# uCCtrl.net
KiCad netlist of a schematic drawn in Altium Designer
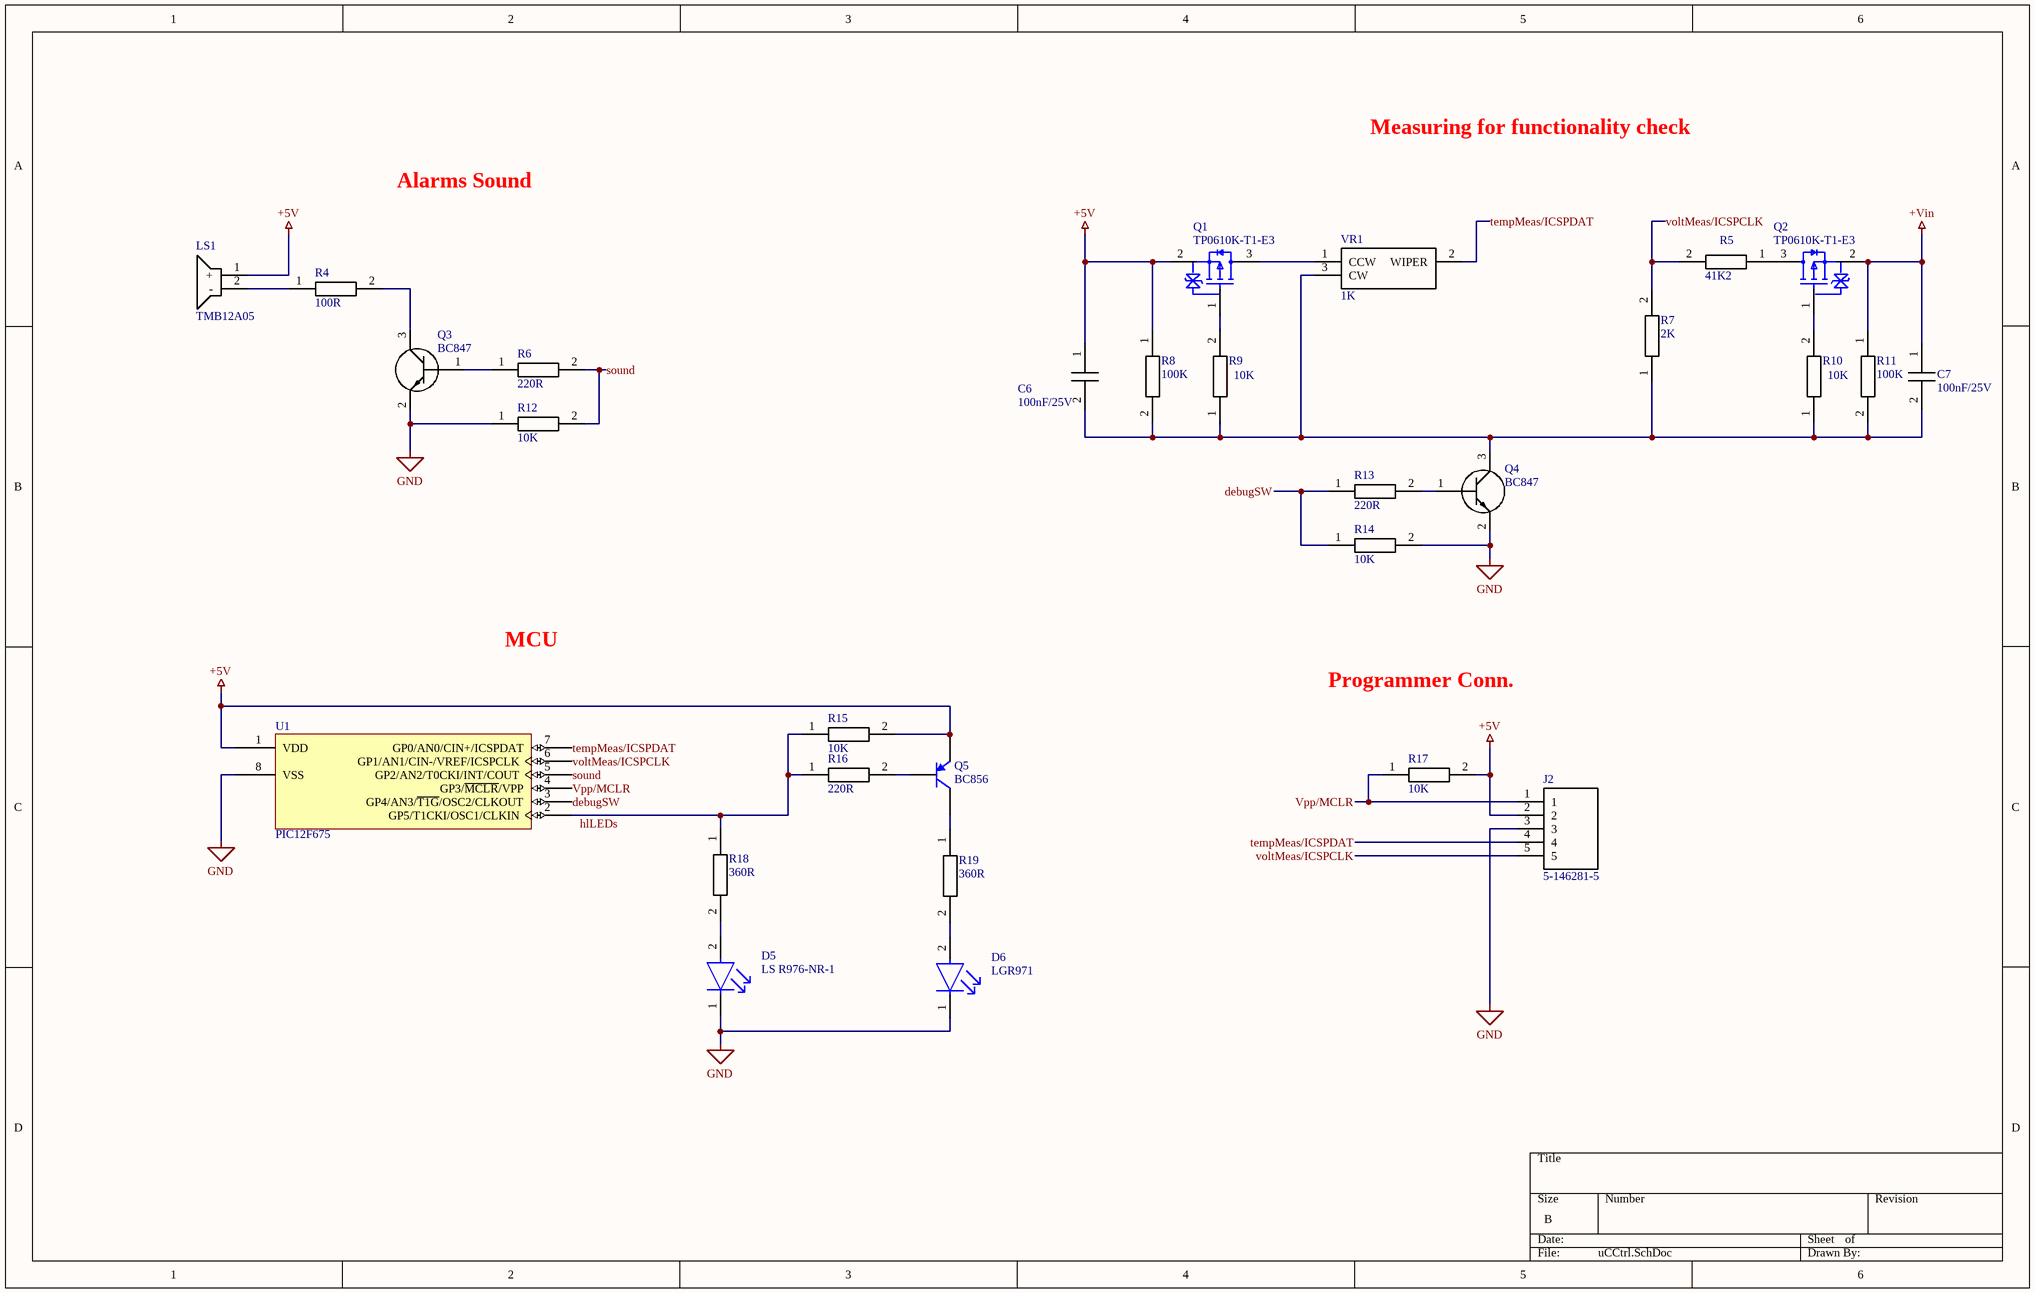
[diagram p0: uCCtrl.SchDoc]

(export (version "E")
  (design (tool "Eeschema 10.0.6"))
  (components
    (comp (ref "C6")
      (value "100nF/25V")
      (footprint "SamacSys:CAPC2012X95N")
      (description "Capacitor")
      (fields (field (name "MANUFACTURER_PART_NUMBER") "GRM219B31E684KA88D"))
      (libsource (lib "*") (part "GRM219B31E684KA88D"))
    )
    (comp (ref "C7")
      (value "100nF/25V")
      (footprint "SamacSys:CAPC2012X95N")
      (description "Capacitor")
      (fields (field (name "MANUFACTURER_PART_NUMBER") "GRM219B31E684KA88D"))
      (libsource (lib "*") (part "GRM219B31E684KA88D"))
    )
    (comp (ref "D5")
      (value "LS R976-NR-1")
      (footprint "FP-LS_R976-MFG")
      (description "LED RED DIFFUSED 0805 SMD")
      (libsource (lib "Altium Content Vault") (part "8706943c75ba83719d021d2fdc84c58"))
    )
    (comp (ref "D6")
      (value "LGR971")
      (footprint "FP-LG_R971-MFG")
      (description "LED GREEN DIFFUSED 0805 SMD")
      (libsource (lib "Altium Content Vault") (part "8706943c75ba83719d021d2fdc84c58"))
    )
    (comp (ref "J2")
      (value "5-146281-5")
      (footprint "SamacSys:HDRV5W67P0X254_1X5_1229X234X821P")
      (description "Connector")
      (fields (field (name "MOUSER PART NUMBER") "571-5-146281-5"))
      (libsource (lib "*") (part "5-146281-5"))
    )
    (comp (ref "LS1")
      (value "TMB12A05")
      (footprint "SamacSys:TMB12A05")
      (description "Loudspeaker or Buzzer")
      (libsource (lib "*") (part "TMB12A05"))
    )
    (comp (ref "Q1")
      (value "TP0610K-T1-E3")
      (footprint "FP-S-03946-MFG")
      (description "MOSFET P-CH 60V 185MA SOT23-3")
      (fields
        (field (name "MANUFACTURER") "Vishay")
        (field (name "OCTOPART") "https://octopart.com/tp0610k-t1-e3-vishay-40944172")
      )
      (libsource (lib "Altium Content Vault") (part "bc9d61678d3f6143cc1ffb3a369bd6c"))
    )
    (comp (ref "Q2")
      (value "TP0610K-T1-E3")
      (footprint "FP-S-03946-MFG")
      (description "MOSFET P-CH 60V 185MA SOT23-3")
      (fields
        (field (name "MANUFACTURER") "Vishay")
        (field (name "OCTOPART") "https://octopart.com/tp0610k-t1-e3-vishay-40944172")
      )
      (libsource (lib "Altium Content Vault") (part "bc9d61678d3f6143cc1ffb3a369bd6c"))
    )
    (comp (ref "Q3")
      (value "BC847")
      (footprint "SamacSys:BC847215")
      (description "Transistor BJT NPN")
      (fields
        (field (name "MANUFACTURER_PART_NUMBER") "BC847,215")
        (field (name "MOUSER PART NUMBER") "771-BC847215")
      )
      (libsource (lib "*") (part "BC847,215"))
    )
    (comp (ref "Q4")
      (value "BC847")
      (footprint "SamacSys:BC847215")
      (description "Transistor BJT NPN")
      (fields
        (field (name "MANUFACTURER_PART_NUMBER") "BC847,215")
        (field (name "MOUSER PART NUMBER") "771-BC847215")
      )
      (libsource (lib "*") (part "BC847,215"))
    )
    (comp (ref "Q5")
      (value "BC856")
      (footprint "NXP-SOT23-3_V")
      (description "PNP General Purpose Transistor, 65 V, -65 to 150 degC, 3-Pin SOT23, RoHS")
      (fields (field (name "MANUFACTURER") "NXP"))
      (libsource (lib "Altium Content Vault") (part "BJT-PNP-BEC-3"))
    )
    (comp (ref "R4")
      (value "100R")
      (footprint "SamacSys:RESC2012X60N")
      (description "Resistor")
      (fields
        (field (name "MANUFACTURER_PART_NUMBER") "CRCW0805100RFKEAHP")
        (field (name "MOUSER PART NUMBER") "71-CRCW0805100RFKEAH")
      )
      (libsource (lib "*") (part "CRCW0805100RFKEAHP"))
    )
    (comp (ref "R5")
      (value "41K2")
      (footprint "SamacSys:RESC2012X65N")
      (description "Resistor")
      (fields (field (name "MANUFACTURER_PART_NUMBER") "CPF0805B41K2E1"))
      (libsource (lib "*") (part "CPF0805B41K2E1"))
    )
    (comp (ref "R6")
      (value "220R")
      (footprint "SamacSys:RESC2012X65N")
      (description "Resistor")
      (fields (field (name "MANUFACTURER_PART_NUMBER") "CPF0805B220RE"))
      (libsource (lib "*") (part "CPF0805B220RE"))
    )
    (comp (ref "R7")
      (value "2K")
      (footprint "SamacSys:RESC2012X65N")
      (description "Resistor")
      (fields
        (field (name "MANUFACTURER_PART_NUMBER") "CPF0805B360RE1")
        (field (name "MOUSER PART NUMBER") "279-CPF0805B360RE1")
      )
      (libsource (lib "*") (part "CPF0805B360RE1"))
    )
    (comp (ref "R8")
      (value "100K")
      (footprint "SamacSys:RESC2012X65N")
      (description "Resistor")
      (fields
        (field (name "MANUFACTURER_PART_NUMBER") "CPF0805B360RE1")
        (field (name "MOUSER PART NUMBER") "279-CPF0805B360RE1")
      )
      (libsource (lib "*") (part "CPF0805B360RE1"))
    )
    (comp (ref "R9")
      (value "10K")
      (footprint "SamacSys:RESC2012X65N")
      (description "Resistor")
      (fields
        (field (name "MANUFACTURER_PART_NUMBER") "CPF0805B360RE1")
        (field (name "MOUSER PART NUMBER") "279-CPF0805B360RE1")
      )
      (libsource (lib "*") (part "CPF0805B360RE1"))
    )
    (comp (ref "R10")
      (value "10K")
      (footprint "SamacSys:RESC2012X65N")
      (description "Resistor")
      (fields
        (field (name "MANUFACTURER_PART_NUMBER") "CPF0805B360RE1")
        (field (name "MOUSER PART NUMBER") "279-CPF0805B360RE1")
      )
      (libsource (lib "*") (part "CPF0805B360RE1"))
    )
    (comp (ref "R11")
      (value "100K")
      (footprint "SamacSys:RESC2012X65N")
      (description "Resistor")
      (fields
        (field (name "MANUFACTURER_PART_NUMBER") "CPF0805B360RE1")
        (field (name "MOUSER PART NUMBER") "279-CPF0805B360RE1")
      )
      (libsource (lib "*") (part "CPF0805B360RE1"))
    )
    (comp (ref "R12")
      (value "10K")
      (footprint "SamacSys:RESC2012X65N")
      (description "Resistor")
      (fields (field (name "MANUFACTURER_PART_NUMBER") "CPF0805B220RE"))
      (libsource (lib "*") (part "CPF0805B220RE"))
    )
    (comp (ref "R13")
      (value "220R")
      (footprint "SamacSys:RESC2012X65N")
      (description "Resistor")
      (fields (field (name "MANUFACTURER_PART_NUMBER") "CPF0805B220RE"))
      (libsource (lib "*") (part "CPF0805B220RE"))
    )
    (comp (ref "R14")
      (value "10K")
      (footprint "SamacSys:RESC2012X65N")
      (description "Resistor")
      (fields (field (name "MANUFACTURER_PART_NUMBER") "CPF0805B220RE"))
      (libsource (lib "*") (part "CPF0805B220RE"))
    )
    (comp (ref "R15")
      (value "10K")
      (footprint "SamacSys:RESC2012X65N")
      (description "Resistor")
      (fields (field (name "MANUFACTURER_PART_NUMBER") "CPF0805B220RE"))
      (libsource (lib "*") (part "CPF0805B220RE"))
    )
    (comp (ref "R16")
      (value "220R")
      (footprint "SamacSys:RESC2012X65N")
      (description "Resistor")
      (fields (field (name "MANUFACTURER_PART_NUMBER") "CPF0805B220RE"))
      (libsource (lib "*") (part "CPF0805B220RE"))
    )
    (comp (ref "R17")
      (value "10K")
      (footprint "SamacSys:RESC2012X65N")
      (description "Resistor")
      (fields
        (field (name "MANUFACTURER_PART_NUMBER") "CPF0805B360RE1")
        (field (name "MOUSER PART NUMBER") "279-CPF0805B360RE1")
      )
      (libsource (lib "*") (part "CPF0805B360RE1"))
    )
    (comp (ref "R18")
      (value "360R")
      (footprint "SamacSys:RESC2012X65N")
      (description "Resistor")
      (fields
        (field (name "MANUFACTURER_PART_NUMBER") "CPF0805B360RE1")
        (field (name "MOUSER PART NUMBER") "279-CPF0805B360RE1")
      )
      (libsource (lib "*") (part "CPF0805B360RE1"))
    )
    (comp (ref "R19")
      (value "360R")
      (footprint "SamacSys:RESC2012X65N")
      (description "Resistor")
      (fields
        (field (name "MANUFACTURER_PART_NUMBER") "CPF0805B360RE1")
        (field (name "MOUSER PART NUMBER") "279-CPF0805B360RE1")
      )
      (libsource (lib "*") (part "CPF0805B360RE1"))
    )
    (comp (ref "U1")
      (value "PIC12F675")
      (footprint "PDIP300-P8")
      (description "FLASH-Based 8-Bit CMOS Microcontroller, 10-Bit A/D, 8-Pin PDIP, Industrial Temperature")
      (libsource (lib "Altium Content Vault") (part "MC-8B-12F675-IL8"))
    )
    (comp (ref "VR1")
      (value "1K")
      (footprint "SamacSys:23SR1KLFTR")
      (description "Variable Resistor")
      (fields (field (name "MANUFACTURER_PART_NUMBER") "23SR1KLFTR"))
      (libsource (lib "*") (part "23SR1KLFTR"))
    )
  )
  (nets
    (net (code "1") (name "+5V") (class "Default")
      (node (ref "C6") (pin "1") (pinfunction "1_1") (pintype "passive"))
      (node (ref "J2") (pin "2") (pinfunction "2_2") (pintype "passive"))
      (node (ref "LS1") (pin "1") (pinfunction "+_1") (pintype "passive"))
      (node (ref "Q1") (pin "2") (pinfunction "S_2") (pintype "passive"))
      (node (ref "Q5") (pin "2") (pinfunction "E_2") (pintype "passive"))
      (node (ref "R15") (pin "2") (pinfunction "2_2") (pintype "passive"))
      (node (ref "R17") (pin "2") (pinfunction "2_2") (pintype "passive"))
      (node (ref "R8") (pin "1") (pinfunction "1_1") (pintype "passive"))
      (node (ref "U1") (pin "1") (pinfunction "VDD_1") (pintype "power_in"))
    )
    (net (code "2") (name "+Vin") (class "Default")
      (node (ref "C7") (pin "1") (pinfunction "1_1") (pintype "passive"))
      (node (ref "Q2") (pin "2") (pinfunction "S_2") (pintype "passive"))
      (node (ref "R11") (pin "1") (pinfunction "1_1") (pintype "passive"))
    )
    (net (code "3") (name "/Vpp{slash}MCLR") (class "Default")
      (node (ref "J2") (pin "1") (pinfunction "1_1") (pintype "passive"))
      (node (ref "R17") (pin "1") (pinfunction "1_1") (pintype "passive"))
      (node (ref "U1") (pin "4") (pinfunction "GP3/~{MCLR}/VPP_4") (pintype "bidirectional"))
    )
    (net (code "4") (name "/debugSW") (class "Default")
      (node (ref "R13") (pin "1") (pinfunction "1_1") (pintype "passive"))
      (node (ref "R14") (pin "1") (pinfunction "1_1") (pintype "passive"))
      (node (ref "U1") (pin "3") (pinfunction "GP4/AN3/~{T1G}/OSC2/CLKOUT_3") (pintype "bidirectional"))
    )
    (net (code "5") (name "/hlLEDs") (class "Default")
      (node (ref "R15") (pin "1") (pinfunction "1_1") (pintype "passive"))
      (node (ref "R16") (pin "1") (pinfunction "1_1") (pintype "passive"))
      (node (ref "R18") (pin "1") (pinfunction "1_1") (pintype "passive"))
      (node (ref "U1") (pin "2") (pinfunction "GP5/T1CKI/OSC1/CLKIN_2") (pintype "bidirectional"))
    )
    (net (code "6") (name "/sound") (class "Default")
      (node (ref "R12") (pin "2") (pinfunction "2_2") (pintype "passive"))
      (node (ref "R6") (pin "2") (pinfunction "2_2") (pintype "passive"))
      (node (ref "U1") (pin "5") (pinfunction "GP2/AN2/T0CKI/INT/COUT_5") (pintype "bidirectional"))
    )
    (net (code "7") (name "/tempMeas{slash}ICSPDAT") (class "Default")
      (node (ref "J2") (pin "4") (pinfunction "4_4") (pintype "passive"))
      (node (ref "U1") (pin "7") (pinfunction "GP0/AN0/CIN+/ICSPDAT_7") (pintype "bidirectional"))
      (node (ref "VR1") (pin "2") (pinfunction "WIPER_2") (pintype "passive"))
    )
    (net (code "8") (name "/voltMeas{slash}ICSPCLK") (class "Default")
      (node (ref "J2") (pin "5") (pinfunction "5_5") (pintype "passive"))
      (node (ref "R5") (pin "2") (pinfunction "2_2") (pintype "passive"))
      (node (ref "R7") (pin "2") (pinfunction "2_2") (pintype "passive"))
      (node (ref "U1") (pin "6") (pinfunction "GP1/AN1/CIN-/VREF/ICSPCLK_6") (pintype "bidirectional"))
    )
    (net (code "9") (name "GND") (class "Default")
      (node (ref "D5") (pin "1") (pinfunction "C_1") (pintype "passive"))
      (node (ref "D6") (pin "1") (pinfunction "C_1") (pintype "passive"))
      (node (ref "J2") (pin "3") (pinfunction "3_3") (pintype "passive"))
      (node (ref "Q3") (pin "2") (pinfunction "E_2") (pintype "passive"))
      (node (ref "Q4") (pin "2") (pinfunction "E_2") (pintype "passive"))
      (node (ref "R12") (pin "1") (pinfunction "1_1") (pintype "passive"))
      (node (ref "R14") (pin "2") (pinfunction "2_2") (pintype "passive"))
      (node (ref "U1") (pin "8") (pinfunction "VSS_8") (pintype "power_in"))
    )
    (net (code "10") (name "Net-(D5-A)") (class "Default")
      (node (ref "D5") (pin "2") (pinfunction "A_2") (pintype "passive"))
      (node (ref "R18") (pin "2") (pinfunction "2_2") (pintype "passive"))
    )
    (net (code "11") (name "Net-(D6-A)") (class "Default")
      (node (ref "D6") (pin "2") (pinfunction "A_2") (pintype "passive"))
      (node (ref "R19") (pin "2") (pinfunction "2_2") (pintype "passive"))
    )
    (net (code "12") (name "Net-(LS1--)") (class "Default")
      (node (ref "LS1") (pin "2") (pinfunction "-_2") (pintype "passive"))
      (node (ref "R4") (pin "1") (pinfunction "1_1") (pintype "passive"))
    )
    (net (code "13") (name "Net-(Q1-D)") (class "Default")
      (node (ref "Q1") (pin "3") (pinfunction "D_3") (pintype "passive"))
      (node (ref "VR1") (pin "1") (pinfunction "CCW_1") (pintype "passive"))
    )
    (net (code "14") (name "Net-(Q1-G)") (class "Default")
      (node (ref "Q1") (pin "1") (pinfunction "G_1") (pintype "passive"))
      (node (ref "R9") (pin "2") (pinfunction "2_2") (pintype "passive"))
    )
    (net (code "15") (name "Net-(Q2-D)") (class "Default")
      (node (ref "Q2") (pin "3") (pinfunction "D_3") (pintype "passive"))
      (node (ref "R5") (pin "1") (pinfunction "1_1") (pintype "passive"))
    )
    (net (code "16") (name "Net-(Q2-G)") (class "Default")
      (node (ref "Q2") (pin "1") (pinfunction "G_1") (pintype "passive"))
      (node (ref "R10") (pin "2") (pinfunction "2_2") (pintype "passive"))
    )
    (net (code "17") (name "Net-(Q3-B)") (class "Default")
      (node (ref "Q3") (pin "1") (pinfunction "B_1") (pintype "passive"))
      (node (ref "R6") (pin "1") (pinfunction "1_1") (pintype "passive"))
    )
    (net (code "18") (name "Net-(Q3-C)") (class "Default")
      (node (ref "Q3") (pin "3") (pinfunction "C_3") (pintype "passive"))
      (node (ref "R4") (pin "2") (pinfunction "2_2") (pintype "passive"))
    )
    (net (code "19") (name "Net-(Q4-B)") (class "Default")
      (node (ref "Q4") (pin "1") (pinfunction "B_1") (pintype "passive"))
      (node (ref "R13") (pin "2") (pinfunction "2_2") (pintype "passive"))
    )
    (net (code "20") (name "Net-(Q4-C)") (class "Default")
      (node (ref "C6") (pin "2") (pinfunction "2_2") (pintype "passive"))
      (node (ref "C7") (pin "2") (pinfunction "2_2") (pintype "passive"))
      (node (ref "Q4") (pin "3") (pinfunction "C_3") (pintype "passive"))
      (node (ref "R10") (pin "1") (pinfunction "1_1") (pintype "passive"))
      (node (ref "R11") (pin "2") (pinfunction "2_2") (pintype "passive"))
      (node (ref "R7") (pin "1") (pinfunction "1_1") (pintype "passive"))
      (node (ref "R8") (pin "2") (pinfunction "2_2") (pintype "passive"))
      (node (ref "R9") (pin "1") (pinfunction "1_1") (pintype "passive"))
      (node (ref "VR1") (pin "3") (pinfunction "CW_3") (pintype "passive"))
    )
    (net (code "21") (name "Net-(Q5-B)") (class "Default")
      (node (ref "Q5") (pin "1") (pinfunction "B_1") (pintype "passive"))
      (node (ref "R16") (pin "2") (pinfunction "2_2") (pintype "passive"))
    )
    (net (code "22") (name "Net-(Q5-C)") (class "Default")
      (node (ref "Q5") (pin "3") (pinfunction "C_3") (pintype "passive"))
      (node (ref "R19") (pin "1") (pinfunction "1_1") (pintype "passive"))
    )
  )
)
